# Sheet1.net
KiCad netlist of a schematic drawn in Altium Designer
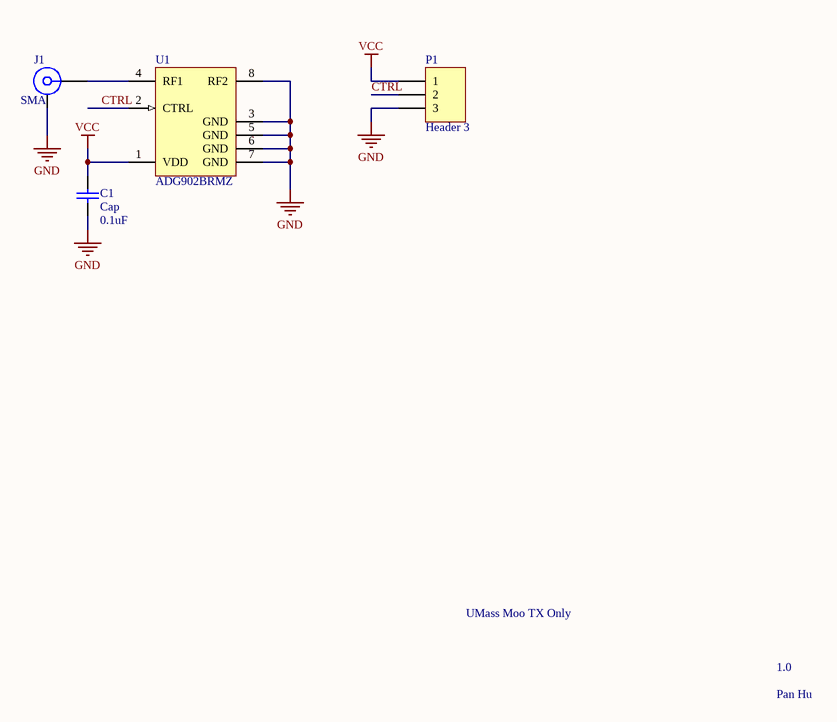
[diagram p0: Sheet1.SchDoc]

(export (version "E")
  (design (tool "Eeschema 10.0.6"))
  (components
    (comp (ref "C1")
      (value "Cap")
      (footprint "1608[0603]")
      (description "Capacitor")
      (fields (field (name "ALTIUM_VALUE") "0.1uF") (field (name "PUBLISHER") "Altium Limited"))
      (libsource (lib "Miscellaneous Devices") (part "Cap"))
    )
    (comp (ref "J1")
      (value "SMA")
      (footprint "ROS-32K101-400L5_V")
      (description "SMA Straight Jack, Up to 18 GHz, -55 to 155 degC")
      (fields (field (name "PARTNUMBER") "32K101-400L5") (field (name "MANUFACTURER") "Rosenberger"))
      (libsource (lib "Altium Content Vault") (part "ROS-CN-1F-RF1"))
    )
    (comp (ref "P1")
      (value "Header 3")
      (footprint "HDR1X3")
      (description "Header, 3-Pin")
      (fields (field (name "PUBLISHER") "Altium Limited"))
      (libsource (lib "Miscellaneous Connectors") (part "Header 3"))
    )
    (comp (ref "U1")
      (value "ADG902BRMZ")
      (footprint "ADI-RM-8_M")
      (libsource (lib "Altium Content Vault") (part "ADI-ADG901-RM-8"))
    )
  )
  (nets
    (net (code "1") (name "/CTRL") (class "Default")
      (node (ref "P1") (pin "2") (pinfunction "2_2") (pintype "passive"))
      (node (ref "U1") (pin "2") (pinfunction "CTRL_2") (pintype "input"))
    )
    (net (code "2") (name "GND") (class "Default")
      (node (ref "C1") (pin "1") (pinfunction "1_1") (pintype "passive"))
      (node (ref "J1") (pin "MH") (pinfunction "MH_MH") (pintype "passive"))
      (node (ref "P1") (pin "3") (pinfunction "3_3") (pintype "passive"))
      (node (ref "U1") (pin "3") (pinfunction "GND_3") (pintype "power_in"))
      (node (ref "U1") (pin "5") (pinfunction "GND_5") (pintype "power_in"))
      (node (ref "U1") (pin "6") (pinfunction "GND_6") (pintype "power_in"))
      (node (ref "U1") (pin "7") (pinfunction "GND_7") (pintype "power_in"))
      (node (ref "U1") (pin "8") (pinfunction "RF2_8") (pintype "passive"))
    )
    (net (code "3") (name "Net-(U1-RF1)") (class "Default")
      (node (ref "J1") (pin "1") (pinfunction "1_1") (pintype "passive"))
      (node (ref "U1") (pin "4") (pinfunction "RF1_4") (pintype "passive"))
    )
    (net (code "4") (name "VCC") (class "Default")
      (node (ref "C1") (pin "2") (pinfunction "2_2") (pintype "passive"))
      (node (ref "P1") (pin "1") (pinfunction "1_1") (pintype "passive"))
      (node (ref "U1") (pin "1") (pinfunction "VDD_1") (pintype "power_in"))
    )
  )
)
